# LED_Controller_UART_Multiplexer.net
KiCad netlist of a schematic drawn in Altium Designer
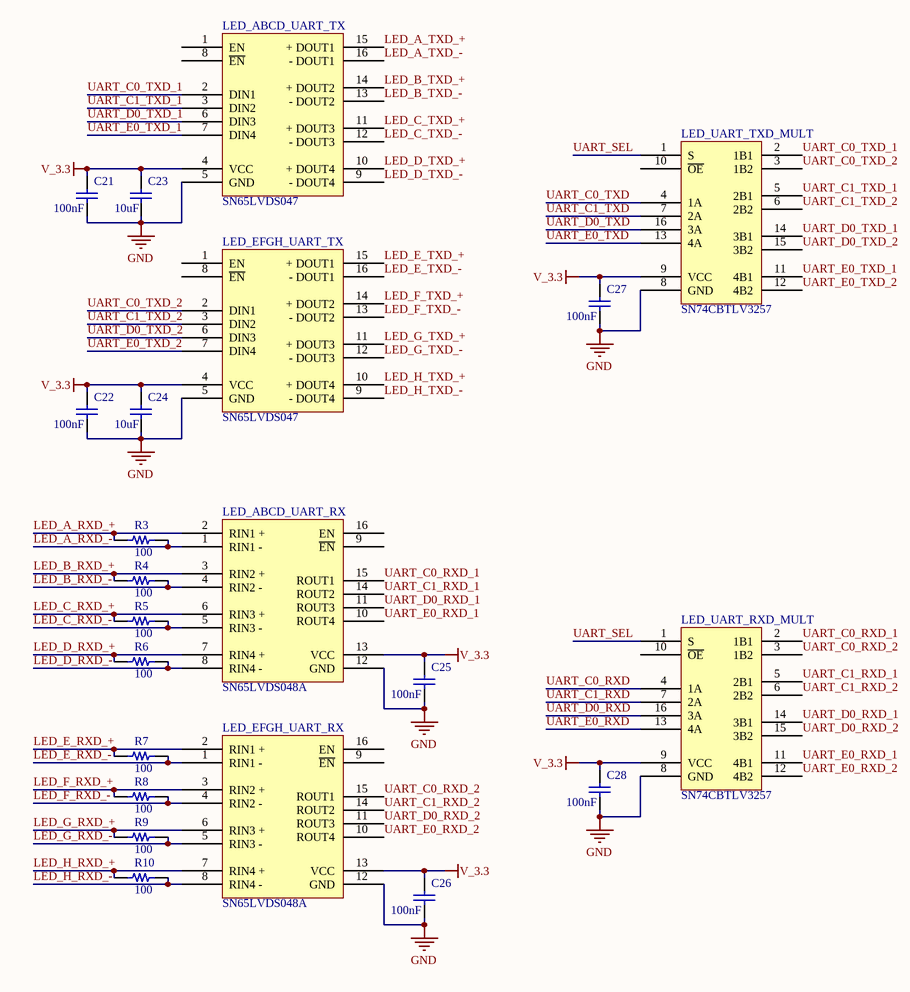
[diagram p0: LED_Controller_UART_Multiplexer.SchDoc]

(export (version "E")
  (design (tool "Eeschema 10.0.6"))
  (components
    (comp (ref "C21")
      (value "100nF")
      (footprint "0603")
      (description "CAP CER .10UF 50V X5R 0603")
      (fields
        (field (name "MANUFACTURER") "AVX Corporation")
        (field (name "MANUFACTURER PART NUMBER") "06035D104KAT2A")
      )
      (libsource (lib "My Schematic Library") (part "CP - 100nF 0603"))
    )
    (comp (ref "C22")
      (value "100nF")
      (footprint "0603")
      (description "CAP CER .10UF 50V X5R 0603")
      (fields
        (field (name "MANUFACTURER") "AVX Corporation")
        (field (name "MANUFACTURER PART NUMBER") "06035D104KAT2A")
      )
      (libsource (lib "My Schematic Library") (part "CP - 100nF 0603"))
    )
    (comp (ref "C23")
      (value "10uF")
      (footprint "0603")
      (description "CAP CER 10000PF 50V X7R 0603")
      (fields
        (field (name "MANUFACTURER") "TDK Corporation")
        (field (name "MANUFACTURER PART NUMBER") "C1608X7R1H103M")
      )
      (libsource (lib "My Schematic Library") (part "CP - 10uF 0603"))
    )
    (comp (ref "C24")
      (value "10uF")
      (footprint "0603")
      (description "CAP CER 10000PF 50V X7R 0603")
      (fields
        (field (name "MANUFACTURER") "TDK Corporation")
        (field (name "MANUFACTURER PART NUMBER") "C1608X7R1H103M")
      )
      (libsource (lib "My Schematic Library") (part "CP - 10uF 0603"))
    )
    (comp (ref "C25")
      (value "100nF")
      (footprint "0603")
      (description "CAP CER .10UF 50V X5R 0603")
      (fields
        (field (name "MANUFACTURER") "AVX Corporation")
        (field (name "MANUFACTURER PART NUMBER") "06035D104KAT2A")
      )
      (libsource (lib "My Schematic Library") (part "CP - 100nF 0603"))
    )
    (comp (ref "C26")
      (value "100nF")
      (footprint "0603")
      (description "CAP CER .10UF 50V X5R 0603")
      (fields
        (field (name "MANUFACTURER") "AVX Corporation")
        (field (name "MANUFACTURER PART NUMBER") "06035D104KAT2A")
      )
      (libsource (lib "My Schematic Library") (part "CP - 100nF 0603"))
    )
    (comp (ref "C27")
      (value "100nF")
      (footprint "0603")
      (description "CAP CER .10UF 50V X5R 0603")
      (fields
        (field (name "MANUFACTURER") "AVX Corporation")
        (field (name "MANUFACTURER PART NUMBER") "06035D104KAT2A")
      )
      (libsource (lib "My Schematic Library") (part "CP - 100nF 0603"))
    )
    (comp (ref "C28")
      (value "100nF")
      (footprint "0603")
      (description "CAP CER .10UF 50V X5R 0603")
      (fields
        (field (name "MANUFACTURER") "AVX Corporation")
        (field (name "MANUFACTURER PART NUMBER") "06035D104KAT2A")
      )
      (libsource (lib "My Schematic Library") (part "CP - 100nF 0603"))
    )
    (comp (ref "LED_ABCD_UART_RX")
      (value "SN65LVDS048A")
      (footprint "TI - PW / TSOP65P640X120-16N")
      (description "LVDS QUAD DIFFERENTIAL LINE RECEIVER")
      (libsource (lib "My Schematic Library") (part "IC - SN65LVDS048A"))
    )
    (comp (ref "LED_ABCD_UART_TX")
      (value "SN65LVDS047")
      (footprint "TI - PW / TSOP65P640X120-16N")
      (description "IC LVDS QUAD LINE DRIVER")
      (libsource (lib "My Schematic Library") (part "IC - SN65LVDS047"))
    )
    (comp (ref "LED_EFGH_UART_RX")
      (value "SN65LVDS048A")
      (footprint "TI - PW / TSOP65P640X120-16N")
      (description "LVDS QUAD DIFFERENTIAL LINE RECEIVER")
      (libsource (lib "My Schematic Library") (part "IC - SN65LVDS048A"))
    )
    (comp (ref "LED_EFGH_UART_TX")
      (value "SN65LVDS047")
      (footprint "TI - PW / TSOP65P640X120-16N")
      (description "IC LVDS QUAD LINE DRIVER")
      (libsource (lib "My Schematic Library") (part "IC - SN65LVDS047"))
    )
    (comp (ref "LED_UART_RXD_MULT")
      (value "SN74CBTLV3257")
      (footprint "TI - DGV16 / TSSOP40P640X120-16N")
      (description "Low-Voltage 4-Bit 1-of-2 FET Multiplexer/Demultiplexer")
      (libsource (lib "My Schematic Library") (part "IC - SN74CBTLV3257"))
    )
    (comp (ref "LED_UART_TXD_MULT")
      (value "SN74CBTLV3257")
      (footprint "TI - DGV16 / TSSOP40P640X120-16N")
      (description "Low-Voltage 4-Bit 1-of-2 FET Multiplexer/Demultiplexer")
      (libsource (lib "My Schematic Library") (part "IC - SN74CBTLV3257"))
    )
    (comp (ref "R3")
      (value "100")
      (footprint "0603")
      (description "RES 100 OHM 1/10W 1% 0603 SMD")
      (libsource (lib "My Schematic Library") (part "RS - 100 0603"))
    )
    (comp (ref "R4")
      (value "100")
      (footprint "0603")
      (description "RES 100 OHM 1/10W 1% 0603 SMD")
      (libsource (lib "My Schematic Library") (part "RS - 100 0603"))
    )
    (comp (ref "R5")
      (value "100")
      (footprint "0603")
      (description "RES 100 OHM 1/10W 1% 0603 SMD")
      (libsource (lib "My Schematic Library") (part "RS - 100 0603"))
    )
    (comp (ref "R6")
      (value "100")
      (footprint "0603")
      (description "RES 100 OHM 1/10W 1% 0603 SMD")
      (libsource (lib "My Schematic Library") (part "RS - 100 0603"))
    )
    (comp (ref "R7")
      (value "100")
      (footprint "0603")
      (description "RES 100 OHM 1/10W 1% 0603 SMD")
      (libsource (lib "My Schematic Library") (part "RS - 100 0603"))
    )
    (comp (ref "R8")
      (value "100")
      (footprint "0603")
      (description "RES 100 OHM 1/10W 1% 0603 SMD")
      (libsource (lib "My Schematic Library") (part "RS - 100 0603"))
    )
    (comp (ref "R9")
      (value "100")
      (footprint "0603")
      (description "RES 100 OHM 1/10W 1% 0603 SMD")
      (libsource (lib "My Schematic Library") (part "RS - 100 0603"))
    )
    (comp (ref "R10")
      (value "100")
      (footprint "0603")
      (description "RES 100 OHM 1/10W 1% 0603 SMD")
      (libsource (lib "My Schematic Library") (part "RS - 100 0603"))
    )
  )
  (nets
    (net (code "1") (name "/LED_A_RXD_+") (class "Default")
      (node (ref "LED_ABCD_UART_RX") (pin "2") (pinfunction "RIN1_+_2") (pintype "passive"))
      (node (ref "R3") (pin "1") (pintype "passive"))
    )
    (net (code "2") (name "/LED_A_RXD_-") (class "Default")
      (node (ref "LED_ABCD_UART_RX") (pin "1") (pinfunction "RIN1_-_1") (pintype "passive"))
      (node (ref "R3") (pin "2") (pintype "passive"))
    )
    (net (code "3") (name "/LED_A_TXD_+") (class "Default")
      (node (ref "LED_ABCD_UART_TX") (pin "15") (pinfunction "+_DOUT1_15") (pintype "passive"))
    )
    (net (code "4") (name "/LED_A_TXD_-") (class "Default")
      (node (ref "LED_ABCD_UART_TX") (pin "16") (pinfunction "-_DOUT1_16") (pintype "passive"))
    )
    (net (code "5") (name "/LED_B_RXD_+") (class "Default")
      (node (ref "LED_ABCD_UART_RX") (pin "3") (pinfunction "RIN2_+_3") (pintype "passive"))
      (node (ref "R4") (pin "1") (pintype "passive"))
    )
    (net (code "6") (name "/LED_B_RXD_-") (class "Default")
      (node (ref "LED_ABCD_UART_RX") (pin "4") (pinfunction "RIN2_-_4") (pintype "passive"))
      (node (ref "R4") (pin "2") (pintype "passive"))
    )
    (net (code "7") (name "/LED_B_TXD_+") (class "Default")
      (node (ref "LED_ABCD_UART_TX") (pin "14") (pinfunction "+_DOUT2_14") (pintype "passive"))
    )
    (net (code "8") (name "/LED_B_TXD_-") (class "Default")
      (node (ref "LED_ABCD_UART_TX") (pin "13") (pinfunction "-_DOUT2_13") (pintype "passive"))
    )
    (net (code "9") (name "/LED_C_RXD_+") (class "Default")
      (node (ref "LED_ABCD_UART_RX") (pin "6") (pinfunction "RIN3_+_6") (pintype "passive"))
      (node (ref "R5") (pin "1") (pintype "passive"))
    )
    (net (code "10") (name "/LED_C_RXD_-") (class "Default")
      (node (ref "LED_ABCD_UART_RX") (pin "5") (pinfunction "RIN3_-_5") (pintype "passive"))
      (node (ref "R5") (pin "2") (pintype "passive"))
    )
    (net (code "11") (name "/LED_C_TXD_+") (class "Default")
      (node (ref "LED_ABCD_UART_TX") (pin "11") (pinfunction "+_DOUT3_11") (pintype "passive"))
    )
    (net (code "12") (name "/LED_C_TXD_-") (class "Default")
      (node (ref "LED_ABCD_UART_TX") (pin "12") (pinfunction "-_DOUT3_12") (pintype "passive"))
    )
    (net (code "13") (name "/LED_D_RXD_+") (class "Default")
      (node (ref "LED_ABCD_UART_RX") (pin "7") (pinfunction "RIN4_+_7") (pintype "passive"))
      (node (ref "R6") (pin "1") (pintype "passive"))
    )
    (net (code "14") (name "/LED_D_RXD_-") (class "Default")
      (node (ref "LED_ABCD_UART_RX") (pin "8") (pinfunction "RIN4_-_8") (pintype "passive"))
      (node (ref "R6") (pin "2") (pintype "passive"))
    )
    (net (code "15") (name "/LED_D_TXD_+") (class "Default")
      (node (ref "LED_ABCD_UART_TX") (pin "10") (pinfunction "+_DOUT4_10") (pintype "passive"))
    )
    (net (code "16") (name "/LED_D_TXD_-") (class "Default")
      (node (ref "LED_ABCD_UART_TX") (pin "9") (pinfunction "-_DOUT4_9") (pintype "passive"))
    )
    (net (code "17") (name "/LED_E_RXD_+") (class "Default")
      (node (ref "LED_EFGH_UART_RX") (pin "2") (pinfunction "RIN1_+_2") (pintype "passive"))
      (node (ref "R7") (pin "1") (pintype "passive"))
    )
    (net (code "18") (name "/LED_E_RXD_-") (class "Default")
      (node (ref "LED_EFGH_UART_RX") (pin "1") (pinfunction "RIN1_-_1") (pintype "passive"))
      (node (ref "R7") (pin "2") (pintype "passive"))
    )
    (net (code "19") (name "/LED_E_TXD_+") (class "Default")
      (node (ref "LED_EFGH_UART_TX") (pin "15") (pinfunction "+_DOUT1_15") (pintype "passive"))
    )
    (net (code "20") (name "/LED_E_TXD_-") (class "Default")
      (node (ref "LED_EFGH_UART_TX") (pin "16") (pinfunction "-_DOUT1_16") (pintype "passive"))
    )
    (net (code "21") (name "/LED_F_RXD_+") (class "Default")
      (node (ref "LED_EFGH_UART_RX") (pin "3") (pinfunction "RIN2_+_3") (pintype "passive"))
      (node (ref "R8") (pin "1") (pintype "passive"))
    )
    (net (code "22") (name "/LED_F_RXD_-") (class "Default")
      (node (ref "LED_EFGH_UART_RX") (pin "4") (pinfunction "RIN2_-_4") (pintype "passive"))
      (node (ref "R8") (pin "2") (pintype "passive"))
    )
    (net (code "23") (name "/LED_F_TXD_+") (class "Default")
      (node (ref "LED_EFGH_UART_TX") (pin "14") (pinfunction "+_DOUT2_14") (pintype "passive"))
    )
    (net (code "24") (name "/LED_F_TXD_-") (class "Default")
      (node (ref "LED_EFGH_UART_TX") (pin "13") (pinfunction "-_DOUT2_13") (pintype "passive"))
    )
    (net (code "25") (name "/LED_G_RXD_+") (class "Default")
      (node (ref "LED_EFGH_UART_RX") (pin "6") (pinfunction "RIN3_+_6") (pintype "passive"))
      (node (ref "R9") (pin "1") (pintype "passive"))
    )
    (net (code "26") (name "/LED_G_RXD_-") (class "Default")
      (node (ref "LED_EFGH_UART_RX") (pin "5") (pinfunction "RIN3_-_5") (pintype "passive"))
      (node (ref "R9") (pin "2") (pintype "passive"))
    )
    (net (code "27") (name "/LED_G_TXD_+") (class "Default")
      (node (ref "LED_EFGH_UART_TX") (pin "11") (pinfunction "+_DOUT3_11") (pintype "passive"))
    )
    (net (code "28") (name "/LED_G_TXD_-") (class "Default")
      (node (ref "LED_EFGH_UART_TX") (pin "12") (pinfunction "-_DOUT3_12") (pintype "passive"))
    )
    (net (code "29") (name "/LED_H_RXD_+") (class "Default")
      (node (ref "LED_EFGH_UART_RX") (pin "7") (pinfunction "RIN4_+_7") (pintype "passive"))
      (node (ref "R10") (pin "1") (pintype "passive"))
    )
    (net (code "30") (name "/LED_H_RXD_-") (class "Default")
      (node (ref "LED_EFGH_UART_RX") (pin "8") (pinfunction "RIN4_-_8") (pintype "passive"))
      (node (ref "R10") (pin "2") (pintype "passive"))
    )
    (net (code "31") (name "/LED_H_TXD_+") (class "Default")
      (node (ref "LED_EFGH_UART_TX") (pin "10") (pinfunction "+_DOUT4_10") (pintype "passive"))
    )
    (net (code "32") (name "/LED_H_TXD_-") (class "Default")
      (node (ref "LED_EFGH_UART_TX") (pin "9") (pinfunction "-_DOUT4_9") (pintype "passive"))
    )
    (net (code "33") (name "/UART_C0_RXD") (class "Default")
      (node (ref "LED_UART_RXD_MULT") (pin "4") (pinfunction "1A_4") (pintype "passive"))
    )
    (net (code "34") (name "/UART_C0_RXD_1") (class "Default")
      (node (ref "LED_ABCD_UART_RX") (pin "15") (pinfunction "ROUT1_15") (pintype "passive"))
      (node (ref "LED_UART_RXD_MULT") (pin "2") (pinfunction "1B1_2") (pintype "passive"))
    )
    (net (code "35") (name "/UART_C0_RXD_2") (class "Default")
      (node (ref "LED_EFGH_UART_RX") (pin "15") (pinfunction "ROUT1_15") (pintype "passive"))
      (node (ref "LED_UART_RXD_MULT") (pin "3") (pinfunction "1B2_3") (pintype "passive"))
    )
    (net (code "36") (name "/UART_C0_TXD") (class "Default")
      (node (ref "LED_UART_TXD_MULT") (pin "4") (pinfunction "1A_4") (pintype "passive"))
    )
    (net (code "37") (name "/UART_C0_TXD_1") (class "Default")
      (node (ref "LED_ABCD_UART_TX") (pin "2") (pinfunction "DIN1_2") (pintype "passive"))
      (node (ref "LED_UART_TXD_MULT") (pin "2") (pinfunction "1B1_2") (pintype "passive"))
    )
    (net (code "38") (name "/UART_C0_TXD_2") (class "Default")
      (node (ref "LED_EFGH_UART_TX") (pin "2") (pinfunction "DIN1_2") (pintype "passive"))
      (node (ref "LED_UART_TXD_MULT") (pin "3") (pinfunction "1B2_3") (pintype "passive"))
    )
    (net (code "39") (name "/UART_C1_RXD") (class "Default")
      (node (ref "LED_UART_RXD_MULT") (pin "7") (pinfunction "2A_7") (pintype "passive"))
    )
    (net (code "40") (name "/UART_C1_RXD_1") (class "Default")
      (node (ref "LED_ABCD_UART_RX") (pin "14") (pinfunction "ROUT2_14") (pintype "passive"))
      (node (ref "LED_UART_RXD_MULT") (pin "5") (pinfunction "2B1_5") (pintype "passive"))
    )
    (net (code "41") (name "/UART_C1_RXD_2") (class "Default")
      (node (ref "LED_EFGH_UART_RX") (pin "14") (pinfunction "ROUT2_14") (pintype "passive"))
      (node (ref "LED_UART_RXD_MULT") (pin "6") (pinfunction "2B2_6") (pintype "passive"))
    )
    (net (code "42") (name "/UART_C1_TXD") (class "Default")
      (node (ref "LED_UART_TXD_MULT") (pin "7") (pinfunction "2A_7") (pintype "passive"))
    )
    (net (code "43") (name "/UART_C1_TXD_1") (class "Default")
      (node (ref "LED_ABCD_UART_TX") (pin "3") (pinfunction "DIN2_3") (pintype "passive"))
      (node (ref "LED_UART_TXD_MULT") (pin "5") (pinfunction "2B1_5") (pintype "passive"))
    )
    (net (code "44") (name "/UART_C1_TXD_2") (class "Default")
      (node (ref "LED_EFGH_UART_TX") (pin "3") (pinfunction "DIN2_3") (pintype "passive"))
      (node (ref "LED_UART_TXD_MULT") (pin "6") (pinfunction "2B2_6") (pintype "passive"))
    )
    (net (code "45") (name "/UART_D0_RXD") (class "Default")
      (node (ref "LED_UART_RXD_MULT") (pin "16") (pinfunction "3A_16") (pintype "passive"))
    )
    (net (code "46") (name "/UART_D0_RXD_1") (class "Default")
      (node (ref "LED_ABCD_UART_RX") (pin "11") (pinfunction "ROUT3_11") (pintype "passive"))
      (node (ref "LED_UART_RXD_MULT") (pin "14") (pinfunction "3B1_14") (pintype "passive"))
    )
    (net (code "47") (name "/UART_D0_RXD_2") (class "Default")
      (node (ref "LED_EFGH_UART_RX") (pin "11") (pinfunction "ROUT3_11") (pintype "passive"))
      (node (ref "LED_UART_RXD_MULT") (pin "15") (pinfunction "3B2_15") (pintype "passive"))
    )
    (net (code "48") (name "/UART_D0_TXD") (class "Default")
      (node (ref "LED_UART_TXD_MULT") (pin "16") (pinfunction "3A_16") (pintype "passive"))
    )
    (net (code "49") (name "/UART_D0_TXD_1") (class "Default")
      (node (ref "LED_ABCD_UART_TX") (pin "6") (pinfunction "DIN3_6") (pintype "passive"))
      (node (ref "LED_UART_TXD_MULT") (pin "14") (pinfunction "3B1_14") (pintype "passive"))
    )
    (net (code "50") (name "/UART_D0_TXD_2") (class "Default")
      (node (ref "LED_EFGH_UART_TX") (pin "6") (pinfunction "DIN3_6") (pintype "passive"))
      (node (ref "LED_UART_TXD_MULT") (pin "15") (pinfunction "3B2_15") (pintype "passive"))
    )
    (net (code "51") (name "/UART_E0_RXD") (class "Default")
      (node (ref "LED_UART_RXD_MULT") (pin "13") (pinfunction "4A_13") (pintype "passive"))
    )
    (net (code "52") (name "/UART_E0_RXD_1") (class "Default")
      (node (ref "LED_ABCD_UART_RX") (pin "10") (pinfunction "ROUT4_10") (pintype "passive"))
      (node (ref "LED_UART_RXD_MULT") (pin "11") (pinfunction "4B1_11") (pintype "passive"))
    )
    (net (code "53") (name "/UART_E0_RXD_2") (class "Default")
      (node (ref "LED_EFGH_UART_RX") (pin "10") (pinfunction "ROUT4_10") (pintype "passive"))
      (node (ref "LED_UART_RXD_MULT") (pin "12") (pinfunction "4B2_12") (pintype "passive"))
    )
    (net (code "54") (name "/UART_E0_TXD") (class "Default")
      (node (ref "LED_UART_TXD_MULT") (pin "13") (pinfunction "4A_13") (pintype "passive"))
    )
    (net (code "55") (name "/UART_E0_TXD_1") (class "Default")
      (node (ref "LED_ABCD_UART_TX") (pin "7") (pinfunction "DIN4_7") (pintype "passive"))
      (node (ref "LED_UART_TXD_MULT") (pin "11") (pinfunction "4B1_11") (pintype "passive"))
    )
    (net (code "56") (name "/UART_E0_TXD_2") (class "Default")
      (node (ref "LED_EFGH_UART_TX") (pin "7") (pinfunction "DIN4_7") (pintype "passive"))
      (node (ref "LED_UART_TXD_MULT") (pin "12") (pinfunction "4B2_12") (pintype "passive"))
    )
    (net (code "57") (name "/UART_SEL") (class "Default")
      (node (ref "LED_UART_RXD_MULT") (pin "1") (pinfunction "S_1") (pintype "passive"))
      (node (ref "LED_UART_TXD_MULT") (pin "1") (pinfunction "S_1") (pintype "passive"))
    )
    (net (code "58") (name "GND") (class "Default")
      (node (ref "C21") (pin "1") (pintype "passive"))
      (node (ref "C22") (pin "1") (pintype "passive"))
      (node (ref "C23") (pin "1") (pintype "passive"))
      (node (ref "C24") (pin "1") (pintype "passive"))
      (node (ref "C25") (pin "1") (pintype "passive"))
      (node (ref "C26") (pin "1") (pintype "passive"))
      (node (ref "C27") (pin "1") (pintype "passive"))
      (node (ref "C28") (pin "1") (pintype "passive"))
      (node (ref "LED_ABCD_UART_RX") (pin "12") (pinfunction "GND_12") (pintype "passive"))
      (node (ref "LED_ABCD_UART_TX") (pin "5") (pinfunction "GND_5") (pintype "passive"))
      (node (ref "LED_EFGH_UART_RX") (pin "12") (pinfunction "GND_12") (pintype "passive"))
      (node (ref "LED_EFGH_UART_TX") (pin "5") (pinfunction "GND_5") (pintype "passive"))
      (node (ref "LED_UART_RXD_MULT") (pin "8") (pinfunction "GND_8") (pintype "passive"))
      (node (ref "LED_UART_TXD_MULT") (pin "8") (pinfunction "GND_8") (pintype "passive"))
    )
    (net (code "59") (name "V_3.3") (class "Default")
      (node (ref "C21") (pin "2") (pintype "passive"))
      (node (ref "C22") (pin "2") (pintype "passive"))
      (node (ref "C23") (pin "2") (pintype "passive"))
      (node (ref "C24") (pin "2") (pintype "passive"))
      (node (ref "C25") (pin "2") (pintype "passive"))
      (node (ref "C26") (pin "2") (pintype "passive"))
      (node (ref "C27") (pin "2") (pintype "passive"))
      (node (ref "C28") (pin "2") (pintype "passive"))
      (node (ref "LED_ABCD_UART_RX") (pin "13") (pinfunction "VCC_13") (pintype "passive"))
      (node (ref "LED_ABCD_UART_TX") (pin "4") (pinfunction "VCC_4") (pintype "passive"))
      (node (ref "LED_EFGH_UART_RX") (pin "13") (pinfunction "VCC_13") (pintype "passive"))
      (node (ref "LED_EFGH_UART_TX") (pin "4") (pinfunction "VCC_4") (pintype "passive"))
      (node (ref "LED_UART_RXD_MULT") (pin "9") (pinfunction "VCC_9") (pintype "passive"))
      (node (ref "LED_UART_TXD_MULT") (pin "9") (pinfunction "VCC_9") (pintype "passive"))
    )
    (net (code "60") (name "unconnected-(LED_ABCD_UART_RX-EN-Pad16)") (class "Default")
      (node (ref "LED_ABCD_UART_RX") (pin "16") (pinfunction "EN_16") (pintype "passive"))
    )
    (net (code "61") (name "unconnected-(LED_ABCD_UART_RX-~{EN}-Pad9)") (class "Default")
      (node (ref "LED_ABCD_UART_RX") (pin "9") (pinfunction "~{EN}_9") (pintype "passive"))
    )
    (net (code "62") (name "unconnected-(LED_ABCD_UART_TX-EN-Pad1)") (class "Default")
      (node (ref "LED_ABCD_UART_TX") (pin "1") (pinfunction "EN_1") (pintype "passive"))
    )
    (net (code "63") (name "unconnected-(LED_ABCD_UART_TX-~{EN}-Pad8)") (class "Default")
      (node (ref "LED_ABCD_UART_TX") (pin "8") (pinfunction "~{EN}_8") (pintype "passive"))
    )
    (net (code "64") (name "unconnected-(LED_EFGH_UART_RX-EN-Pad16)") (class "Default")
      (node (ref "LED_EFGH_UART_RX") (pin "16") (pinfunction "EN_16") (pintype "passive"))
    )
    (net (code "65") (name "unconnected-(LED_EFGH_UART_RX-~{EN}-Pad9)") (class "Default")
      (node (ref "LED_EFGH_UART_RX") (pin "9") (pinfunction "~{EN}_9") (pintype "passive"))
    )
    (net (code "66") (name "unconnected-(LED_EFGH_UART_TX-EN-Pad1)") (class "Default")
      (node (ref "LED_EFGH_UART_TX") (pin "1") (pinfunction "EN_1") (pintype "passive"))
    )
    (net (code "67") (name "unconnected-(LED_EFGH_UART_TX-~{EN}-Pad8)") (class "Default")
      (node (ref "LED_EFGH_UART_TX") (pin "8") (pinfunction "~{EN}_8") (pintype "passive"))
    )
    (net (code "68") (name "unconnected-(LED_UART_RXD_MULT-~{OE}-Pad10)") (class "Default")
      (node (ref "LED_UART_RXD_MULT") (pin "10") (pinfunction "~{OE}_10") (pintype "passive"))
    )
    (net (code "69") (name "unconnected-(LED_UART_TXD_MULT-~{OE}-Pad10)") (class "Default")
      (node (ref "LED_UART_TXD_MULT") (pin "10") (pinfunction "~{OE}_10") (pintype "passive"))
    )
  )
)
